# PAM_Interface.net
KiCad netlist of a schematic drawn in Altium Designer
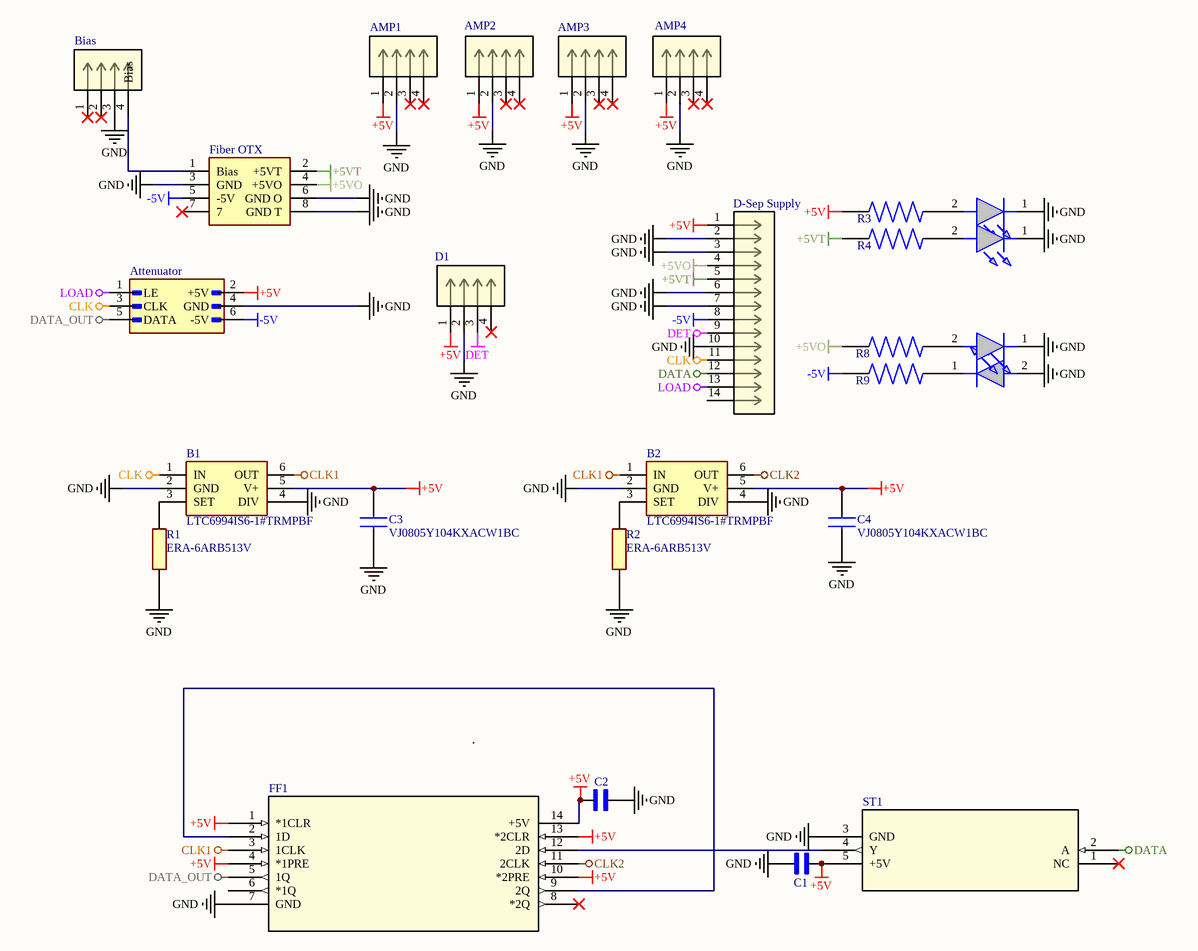
[diagram p0: PAM_Interface.SchDoc]

(export (version "E")
  (design (tool "Eeschema 10.0.6"))
  (components
    (comp (ref "+5VO")
      (value "SML-LX1206GW-TR")
      (footprint "LEDC3216X110N")
      (description "LUMEX - SML-LX1206GW-TR - LED, 2MM X 1.6MM, GREEN, 10MCD, 565NM")
      (fields (field (name "MOUSER PART NUMBER") "696-SML-LX1206GW"))
      (libsource (lib "LEDGreen") (part "SML-LX1206GW-TR"))
    )
    (comp (ref "+5VT")
      (value "SML-LX1206GW-TR")
      (footprint "LEDC3216X110N")
      (description "LUMEX - SML-LX1206GW-TR - LED, 2MM X 1.6MM, GREEN, 10MCD, 565NM")
      (fields (field (name "MOUSER PART NUMBER") "696-SML-LX1206GW"))
      (libsource (lib "LEDGreen") (part "SML-LX1206GW-TR"))
    )
    (comp (ref "-5V")
      (value "SML-LX1206GW-TR")
      (footprint "LEDC3216X110N")
      (description "LUMEX - SML-LX1206GW-TR - LED, 2MM X 1.6MM, GREEN, 10MCD, 565NM")
      (fields (field (name "MOUSER PART NUMBER") "696-SML-LX1206GW"))
      (libsource (lib "LEDGreen") (part "SML-LX1206GW-TR"))
    )
    (comp (ref "AMP1")
      (value "DF11-4DP-2DSA(24)")
      (footprint "CON4_2X2_UF_DF11_HIR")
      (description "No Description Available")
      (fields (field (name "COPYRIGHT") "Copyright (C) 2025 Ultra Librarian. All rights reserved."))
      (libsource (lib "DF11-4DP-2DSA24") (part "DF11-4DP-2DSA24"))
    )
    (comp (ref "AMP2")
      (value "DF11-4DP-2DSA(24)")
      (footprint "CON4_2X2_UF_DF11_HIR")
      (description "No Description Available")
      (fields (field (name "COPYRIGHT") "Copyright (C) 2025 Ultra Librarian. All rights reserved."))
      (libsource (lib "DF11-4DP-2DSA24") (part "DF11-4DP-2DSA24"))
    )
    (comp (ref "AMP3")
      (value "DF11-4DP-2DSA(24)")
      (footprint "CON4_2X2_UF_DF11_HIR")
      (description "No Description Available")
      (fields (field (name "COPYRIGHT") "Copyright (C) 2025 Ultra Librarian. All rights reserved."))
      (libsource (lib "DF11-4DP-2DSA24") (part "DF11-4DP-2DSA24"))
    )
    (comp (ref "AMP4")
      (value "DF11-4DP-2DSA(24)")
      (footprint "CON4_2X2_UF_DF11_HIR")
      (description "No Description Available")
      (fields (field (name "COPYRIGHT") "Copyright (C) 2025 Ultra Librarian. All rights reserved."))
      (libsource (lib "DF11-4DP-2DSA24") (part "DF11-4DP-2DSA24"))
    )
    (comp (ref "Attenuator")
      (value "DF11-6DP-2DSA(24)")
      (footprint "HIROSE_DF11-6DP-2DSA(24)")
      (description "Connector Header Through Hole 6 position 0.079 (2.00mm)")
      (fields (field (name "MF") "Hirose Electric Co Ltd"))
      (libsource (lib "DF11-6DP-2DSA_24_") (part "DF11-6DP-2DSA(24)"))
    )
    (comp (ref "B1")
      (value "LTC6994IS6-1#TRMPBF")
      (footprint "SOT95P280X100-6N")
      (description "Timer, 2.25 ??5.5 V, 6-pin TSOT-23%0%0")
      (fields (field (name "MOUSER PART NUMBER") "584-C6994IS6-1TRMPBF"))
      (libsource (lib "LTC6994IS6-1#TRMPBF") (part "LTC6994IS6-1#TRMPBF"))
    )
    (comp (ref "B2")
      (value "LTC6994IS6-1#TRMPBF")
      (footprint "SOT95P280X100-6N")
      (description "Timer, 2.25 ??5.5 V, 6-pin TSOT-23%0%0")
      (fields (field (name "MOUSER PART NUMBER") "584-C6994IS6-1TRMPBF"))
      (libsource (lib "LTC6994IS6-1#TRMPBF") (part "LTC6994IS6-1#TRMPBF"))
    )
    (comp (ref "Bias")
      (value "DF11-4DP-2DSA(24)")
      (footprint "CON4_2X2_UF_DF11_HIR")
      (description "No Description Available")
      (fields (field (name "COPYRIGHT") "Copyright (C) 2025 Ultra Librarian. All rights reserved."))
      (libsource (lib "") (part "DF11-4DP-2DSA24_2"))
    )
    (comp (ref "C1")
      (value "VJ0805Y104KXQCW1BC")
      (footprint "CAPC2012X145N")
      (fields (field (name "MF") "{'manufacturer': u'Vishay Vitramon'}"))
      (libsource (lib "VJ0805Y104KXQCW1BC") (part "VJ0805Y104KXQCW1BC"))
    )
    (comp (ref "C2")
      (value "VJ0805Y104KXQCW1BC")
      (footprint "CAPC2012X145N")
      (fields (field (name "MF") "{'manufacturer': u'Vishay Vitramon'}"))
      (libsource (lib "VJ0805Y104KXQCW1BC") (part "VJ0805Y104KXQCW1BC"))
    )
    (comp (ref "C3")
      (value "VJ0805Y104KXACW1BC")
      (footprint "CAPC2012X70N")
      (description "VISHAY - VJ0805Y104KXACW1BC - CAP, MLCC, X7R, 0.1UF, 50V, 0805")
      (fields (field (name "MOUSER PART NUMBER") "71-VJ0805Y104KXACWBC"))
      (libsource (lib "VJ0805Y104KXACW1BC") (part "VJ0805Y104KXACW1BC"))
    )
    (comp (ref "C4")
      (value "VJ0805Y104KXACW1BC")
      (footprint "CAPC2012X70N")
      (description "VISHAY - VJ0805Y104KXACW1BC - CAP, MLCC, X7R, 0.1UF, 50V, 0805")
      (fields (field (name "MOUSER PART NUMBER") "71-VJ0805Y104KXACWBC"))
      (libsource (lib "VJ0805Y104KXACW1BC") (part "VJ0805Y104KXACW1BC"))
    )
    (comp (ref "D-Sep Supply")
      (value "DF11-14DP-2DSA(24)")
      (footprint "CON14_2X7_UF_DF11_HIR")
      (description "No Description Available")
      (fields (field (name "COPYRIGHT") "Copyright (C) 2025 Ultra Librarian. All rights reserved."))
      (libsource (lib "DF11-14DP-2DSA24") (part "DF11-14DP-2DSA24"))
    )
    (comp (ref "D1")
      (value "DF11-4DP-2DSA(24)")
      (footprint "CON4_2X2_UF_DF11_HIR")
      (description "No Description Available")
      (fields (field (name "COPYRIGHT") "Copyright (C) 2025 Ultra Librarian. All rights reserved."))
      (libsource (lib "") (part "DF11-4DP-2DSA24_1"))
    )
    (comp (ref "FF1")
      (value "SN74ACT74PWRQ1")
      (footprint "PW14")
      (description "Dual Positive-Edge-Triggered D-Type Flip-Flops With Clear and Preset 14-TSSOP -40 to 125")
      (fields
        (field (name "MANUFACTURER_PART_NUMBER") "SN74ACT74PWR")
        (field (name "COPYRIGHT") "Copyright (C) 2025 Ultra Librarian. All rights reserved.")
      )
      (libsource (lib "SN74ACT74PWR") (part "SN74ACT74PWR"))
    )
    (comp (ref "Fiber OTX")
      (value "DF11-8DP-2DSA(24)")
      (footprint "HIROSE_DF11-8DP-2DSA(24)")
      (description "Connector Header Through Hole 8 position 0.079 (2.00mm)")
      (fields (field (name "MF") "Hirose Electric"))
      (libsource (lib "DF11-8DP-2DSA_24_") (part "DF11-8DP-2DSA(24)"))
    )
    (comp (ref "LED1")
      (value "SML-LX1206GW-TR")
      (footprint "LEDC3216X110N")
      (description "LUMEX - SML-LX1206GW-TR - LED, 2MM X 1.6MM, GREEN, 10MCD, 565NM")
      (fields (field (name "MOUSER PART NUMBER") "696-SML-LX1206GW"))
      (libsource (lib "LEDGreen") (part "SML-LX1206GW-TR"))
    )
    (comp (ref "R1")
      (value "ERA-6ARB513V")
      (footprint "ERA6AEB101V")
      (description "Metal Thin Film Chip Resistor, 0805, 0.125W")
      (libsource (lib "ERA-6ARB513V") (part "ERA-6ARB513V"))
    )
    (comp (ref "R2")
      (value "ERA-6ARB513V")
      (footprint "ERA6AEB101V")
      (description "Metal Thin Film Chip Resistor, 0805, 0.125W")
      (libsource (lib "ERA-6ARB513V") (part "ERA-6ARB513V"))
    )
    (comp (ref "R3")
      (value "ERA6VEB1000V")
      (footprint "RES_ERA6VEB1000V")
      (libsource (lib "ERA6VEB1000V") (part "ERA6VEB1000V"))
    )
    (comp (ref "R4")
      (value "ERA6VEB1000V")
      (footprint "RES_ERA6VEB1000V")
      (libsource (lib "ERA6VEB1000V") (part "ERA6VEB1000V"))
    )
    (comp (ref "R8")
      (value "ERA6VEB1000V")
      (footprint "RES_ERA6VEB1000V")
      (libsource (lib "ERA6VEB1000V") (part "ERA6VEB1000V"))
    )
    (comp (ref "R9")
      (value "ERA6VEB1000V")
      (footprint "RES_ERA6VEB1000V")
      (libsource (lib "ERA6VEB1000V") (part "ERA6VEB1000V"))
    )
    (comp (ref "ST1")
      (value "SN74LVC1G17DBVR")
      (footprint "DBV5")
      (description "Single 1.65-V to 5.5-V buffer with Schmitt-Trigger inputs 5-SOT-23 -40 to 125")
      (fields (field (name "COPYRIGHT") "Copyright (C) 2025 Ultra Librarian. All rights reserved."))
      (libsource (lib "SN74LVC1G17DBVR") (part "SN74LVC1G17DBVR"))
    )
  )
  (nets
    (net (code "1") (name "+5V") (class "Default")
      (node (ref "AMP1") (pin "1") (pinfunction "+5V_1") (pintype "passive"))
      (node (ref "AMP2") (pin "1") (pinfunction "+5V_1") (pintype "passive"))
      (node (ref "AMP3") (pin "1") (pinfunction "+5V_1") (pintype "passive"))
      (node (ref "AMP4") (pin "1") (pinfunction "+5V_1") (pintype "passive"))
      (node (ref "Attenuator") (pin "2") (pinfunction "+5V_2") (pintype "passive"))
      (node (ref "B1") (pin "5") (pinfunction "V+_5") (pintype "passive"))
      (node (ref "B2") (pin "5") (pinfunction "V+_5") (pintype "passive"))
      (node (ref "C1") (pin "2") (pinfunction "2_2") (pintype "passive"))
      (node (ref "C2") (pin "1") (pinfunction "1_1") (pintype "passive"))
      (node (ref "C3") (pin "2") (pinfunction "2_2") (pintype "passive"))
      (node (ref "C4") (pin "2") (pinfunction "2_2") (pintype "passive"))
      (node (ref "D-Sep Supply") (pin "1") (pinfunction "+5V_1") (pintype "passive"))
      (node (ref "D1") (pin "1") (pinfunction "+5V_1") (pintype "passive"))
      (node (ref "FF1") (pin "1") (pinfunction "*1CLR_1") (pintype "input"))
      (node (ref "FF1") (pin "10") (pinfunction "*2PRE_10") (pintype "input"))
      (node (ref "FF1") (pin "13") (pinfunction "*2CLR_13") (pintype "input"))
      (node (ref "FF1") (pin "14") (pinfunction "+5V_14") (pintype "power_in"))
      (node (ref "FF1") (pin "4") (pinfunction "*1PRE_4") (pintype "input"))
      (node (ref "R3") (pin "1") (pinfunction "1_1") (pintype "passive"))
      (node (ref "ST1") (pin "5") (pinfunction "+5V_5") (pintype "power_in"))
    )
    (net (code "2") (name "+5VO") (class "Default")
      (node (ref "D-Sep Supply") (pin "4") (pinfunction "GND_4") (pintype "passive"))
      (node (ref "Fiber OTX") (pin "4") (pinfunction "+5VO_4") (pintype "passive"))
      (node (ref "R8") (pin "1") (pinfunction "1_1") (pintype "passive"))
    )
    (net (code "3") (name "+5VT") (class "Default")
      (node (ref "D-Sep Supply") (pin "5") (pinfunction "DET_5") (pintype "passive"))
      (node (ref "Fiber OTX") (pin "2") (pinfunction "+5VT_2") (pintype "passive"))
      (node (ref "R4") (pin "2") (pinfunction "2_2") (pintype "passive"))
    )
    (net (code "4") (name "-5V") (class "Default")
      (node (ref "Attenuator") (pin "6") (pinfunction "-5V_6") (pintype "passive"))
      (node (ref "D-Sep Supply") (pin "8") (pinfunction "NC_8") (pintype "passive"))
      (node (ref "Fiber OTX") (pin "5") (pinfunction "-5V_5") (pintype "passive"))
      (node (ref "R9") (pin "1") (pinfunction "1_1") (pintype "passive"))
    )
    (net (code "5") (name "CLK") (class "Default")
      (node (ref "Attenuator") (pin "3") (pinfunction "CLK_3") (pintype "passive"))
      (node (ref "B1") (pin "1") (pinfunction "IN_1") (pintype "passive"))
      (node (ref "D-Sep Supply") (pin "11") (pinfunction "GND_11") (pintype "passive"))
    )
    (net (code "6") (name "CLK1") (class "Default")
      (node (ref "B1") (pin "6") (pinfunction "OUT_6") (pintype "passive"))
      (node (ref "B2") (pin "1") (pinfunction "IN_1") (pintype "passive"))
      (node (ref "FF1") (pin "3") (pinfunction "1CLK_3") (pintype "input"))
    )
    (net (code "7") (name "CLK2") (class "Default")
      (node (ref "B2") (pin "6") (pinfunction "OUT_6") (pintype "passive"))
      (node (ref "FF1") (pin "11") (pinfunction "2CLK_11") (pintype "input"))
    )
    (net (code "8") (name "DATA") (class "Default")
      (node (ref "D-Sep Supply") (pin "12") (pinfunction "-5V_12") (pintype "passive"))
      (node (ref "ST1") (pin "2") (pinfunction "A_2") (pintype "input"))
    )
    (net (code "9") (name "DATA_OUT") (class "Default")
      (node (ref "Attenuator") (pin "5") (pinfunction "DATA_5") (pintype "passive"))
      (node (ref "FF1") (pin "5") (pinfunction "1Q_5") (pintype "output"))
    )
    (net (code "10") (name "DET") (class "Default")
      (node (ref "D-Sep Supply") (pin "9") (pinfunction "GND_9") (pintype "passive"))
      (node (ref "D1") (pin "3") (pinfunction "DET_3") (pintype "passive"))
    )
    (net (code "11") (name "GND") (class "Default")
      (node (ref "+5VO") (pin "1") (pinfunction "K_1") (pintype "passive"))
      (node (ref "+5VT") (pin "1") (pinfunction "K_1") (pintype "passive"))
      (node (ref "-5V") (pin "2") (pinfunction "A_2") (pintype "passive"))
      (node (ref "AMP1") (pin "2") (pinfunction "GND_2") (pintype "passive"))
      (node (ref "AMP2") (pin "2") (pinfunction "GND_2") (pintype "passive"))
      (node (ref "AMP3") (pin "2") (pinfunction "GND_2") (pintype "passive"))
      (node (ref "AMP4") (pin "2") (pinfunction "GND_2") (pintype "passive"))
      (node (ref "Attenuator") (pin "4") (pinfunction "GND_4") (pintype "passive"))
      (node (ref "B1") (pin "2") (pinfunction "GND_2") (pintype "passive"))
      (node (ref "B1") (pin "4") (pinfunction "DIV_4") (pintype "passive"))
      (node (ref "B2") (pin "2") (pinfunction "GND_2") (pintype "passive"))
      (node (ref "B2") (pin "4") (pinfunction "DIV_4") (pintype "passive"))
      (node (ref "Bias") (pin "3") (pinfunction "GND_3") (pintype "passive"))
      (node (ref "C1") (pin "1") (pinfunction "1_1") (pintype "passive"))
      (node (ref "C2") (pin "2") (pinfunction "2_2") (pintype "passive"))
      (node (ref "D-Sep Supply") (pin "10") (pinfunction "+5V_OTX_10") (pintype "passive"))
      (node (ref "D-Sep Supply") (pin "2") (pinfunction "GND_2") (pintype "passive"))
      (node (ref "D-Sep Supply") (pin "3") (pinfunction "+5V_TEC_3") (pintype "passive"))
      (node (ref "D-Sep Supply") (pin "6") (pinfunction "CLK_6") (pintype "passive"))
      (node (ref "D-Sep Supply") (pin "7") (pinfunction "LOAD_7") (pintype "passive"))
      (node (ref "D1") (pin "2") (pinfunction "GND_2") (pintype "passive"))
      (node (ref "FF1") (pin "7") (pinfunction "GND_7") (pintype "power_in"))
      (node (ref "Fiber OTX") (pin "3") (pinfunction "GND_3") (pintype "passive"))
      (node (ref "Fiber OTX") (pin "6") (pinfunction "GND_O_6") (pintype "passive"))
      (node (ref "Fiber OTX") (pin "8") (pinfunction "GND_T_8") (pintype "passive"))
      (node (ref "LED1") (pin "1") (pinfunction "K_1") (pintype "passive"))
      (node (ref "R1") (pin "2") (pinfunction "2_2") (pintype "passive"))
      (node (ref "R2") (pin "2") (pinfunction "2_2") (pintype "passive"))
      (node (ref "ST1") (pin "3") (pinfunction "GND_3") (pintype "power_in"))
    )
    (net (code "12") (name "LOAD") (class "Default")
      (node (ref "Attenuator") (pin "1") (pinfunction "LE_1") (pintype "passive"))
      (node (ref "D-Sep Supply") (pin "13") (pinfunction "GND_13") (pintype "passive"))
    )
    (net (code "13") (name "Net-(+5VO-A)") (class "Default")
      (node (ref "+5VO") (pin "2") (pinfunction "A_2") (pintype "passive"))
      (node (ref "R8") (pin "2") (pinfunction "2_2") (pintype "passive"))
    )
    (net (code "14") (name "Net-(+5VT-A)") (class "Default")
      (node (ref "+5VT") (pin "2") (pinfunction "A_2") (pintype "passive"))
      (node (ref "R4") (pin "1") (pinfunction "1_1") (pintype "passive"))
    )
    (net (code "15") (name "Net-(-5V-K)") (class "Default")
      (node (ref "-5V") (pin "1") (pinfunction "K_1") (pintype "passive"))
      (node (ref "R9") (pin "2") (pinfunction "2_2") (pintype "passive"))
    )
    (net (code "16") (name "Net-(B1-SET)") (class "Default")
      (node (ref "B1") (pin "3") (pinfunction "SET_3") (pintype "passive"))
      (node (ref "R1") (pin "1") (pinfunction "1_1") (pintype "passive"))
    )
    (net (code "17") (name "Net-(B2-SET)") (class "Default")
      (node (ref "B2") (pin "3") (pinfunction "SET_3") (pintype "passive"))
      (node (ref "R2") (pin "1") (pinfunction "1_1") (pintype "passive"))
    )
    (net (code "18") (name "Net-(Bias-Bias)") (class "Default")
      (node (ref "Bias") (pin "4") (pinfunction "Bias_4") (pintype "passive"))
      (node (ref "Fiber OTX") (pin "1") (pinfunction "Bias_1") (pintype "passive"))
    )
    (net (code "19") (name "Net-(FF1-1D)") (class "Default")
      (node (ref "FF1") (pin "2") (pinfunction "1D_2") (pintype "input"))
      (node (ref "FF1") (pin "9") (pinfunction "2Q_9") (pintype "output"))
    )
    (net (code "20") (name "Net-(FF1-2D)") (class "Default")
      (node (ref "FF1") (pin "12") (pinfunction "2D_12") (pintype "input"))
      (node (ref "ST1") (pin "4") (pinfunction "Y_4") (pintype "output"))
    )
    (net (code "21") (name "Net-(LED1-A)") (class "Default")
      (node (ref "LED1") (pin "2") (pinfunction "A_2") (pintype "passive"))
      (node (ref "R3") (pin "2") (pinfunction "2_2") (pintype "passive"))
    )
    (net (code "22") (name "unconnected-(AMP1-Pad3)") (class "Default")
      (node (ref "AMP1") (pin "3") (pinfunction "3_3") (pintype "passive+no_connect"))
    )
    (net (code "23") (name "unconnected-(AMP1-Pad4)") (class "Default")
      (node (ref "AMP1") (pin "4") (pinfunction "4_4") (pintype "passive+no_connect"))
    )
    (net (code "24") (name "unconnected-(AMP2-Pad3)") (class "Default")
      (node (ref "AMP2") (pin "3") (pinfunction "3_3") (pintype "passive+no_connect"))
    )
    (net (code "25") (name "unconnected-(AMP2-Pad4)") (class "Default")
      (node (ref "AMP2") (pin "4") (pinfunction "4_4") (pintype "passive+no_connect"))
    )
    (net (code "26") (name "unconnected-(AMP3-Pad3)") (class "Default")
      (node (ref "AMP3") (pin "3") (pinfunction "3_3") (pintype "passive+no_connect"))
    )
    (net (code "27") (name "unconnected-(AMP3-Pad4)") (class "Default")
      (node (ref "AMP3") (pin "4") (pinfunction "4_4") (pintype "passive+no_connect"))
    )
    (net (code "28") (name "unconnected-(AMP4-Pad3)") (class "Default")
      (node (ref "AMP4") (pin "3") (pinfunction "3_3") (pintype "passive+no_connect"))
    )
    (net (code "29") (name "unconnected-(AMP4-Pad4)") (class "Default")
      (node (ref "AMP4") (pin "4") (pinfunction "4_4") (pintype "passive+no_connect"))
    )
    (net (code "30") (name "unconnected-(Bias-Pad1)") (class "Default")
      (node (ref "Bias") (pin "1") (pinfunction "1_1") (pintype "passive+no_connect"))
    )
    (net (code "31") (name "unconnected-(Bias-Pad2)") (class "Default")
      (node (ref "Bias") (pin "2") (pinfunction "2_2") (pintype "passive+no_connect"))
    )
    (net (code "32") (name "unconnected-(C3-Pad1)") (class "Default")
      (node (ref "C3") (pin "1") (pinfunction "1_1") (pintype "passive"))
    )
    (net (code "33") (name "unconnected-(C4-Pad1)") (class "Default")
      (node (ref "C4") (pin "1") (pinfunction "1_1") (pintype "passive"))
    )
    (net (code "34") (name "unconnected-(D-Sep Supply-DATA-Pad14)") (class "Default")
      (node (ref "D-Sep Supply") (pin "14") (pinfunction "DATA_14") (pintype "passive"))
    )
    (net (code "35") (name "unconnected-(D1-Pad4)") (class "Default")
      (node (ref "D1") (pin "4") (pinfunction "4_4") (pintype "passive+no_connect"))
    )
    (net (code "36") (name "unconnected-(FF1-*1Q-Pad6)") (class "Default")
      (node (ref "FF1") (pin "6") (pinfunction "*1Q_6") (pintype "output"))
    )
    (net (code "37") (name "unconnected-(FF1-*2Q-Pad8)") (class "Default")
      (node (ref "FF1") (pin "8") (pinfunction "*2Q_8") (pintype "output+no_connect"))
    )
    (net (code "38") (name "unconnected-(Fiber OTX-Pad7)") (class "Default")
      (node (ref "Fiber OTX") (pin "7") (pinfunction "7_7") (pintype "passive+no_connect"))
    )
    (net (code "39") (name "unconnected-(ST1-NC-Pad1)") (class "Default")
      (node (ref "ST1") (pin "1") (pinfunction "NC_1") (pintype "passive+no_connect"))
    )
  )
)
